# Logic_IO_Protection.net
KiCad netlist of a schematic drawn in Altium Designer
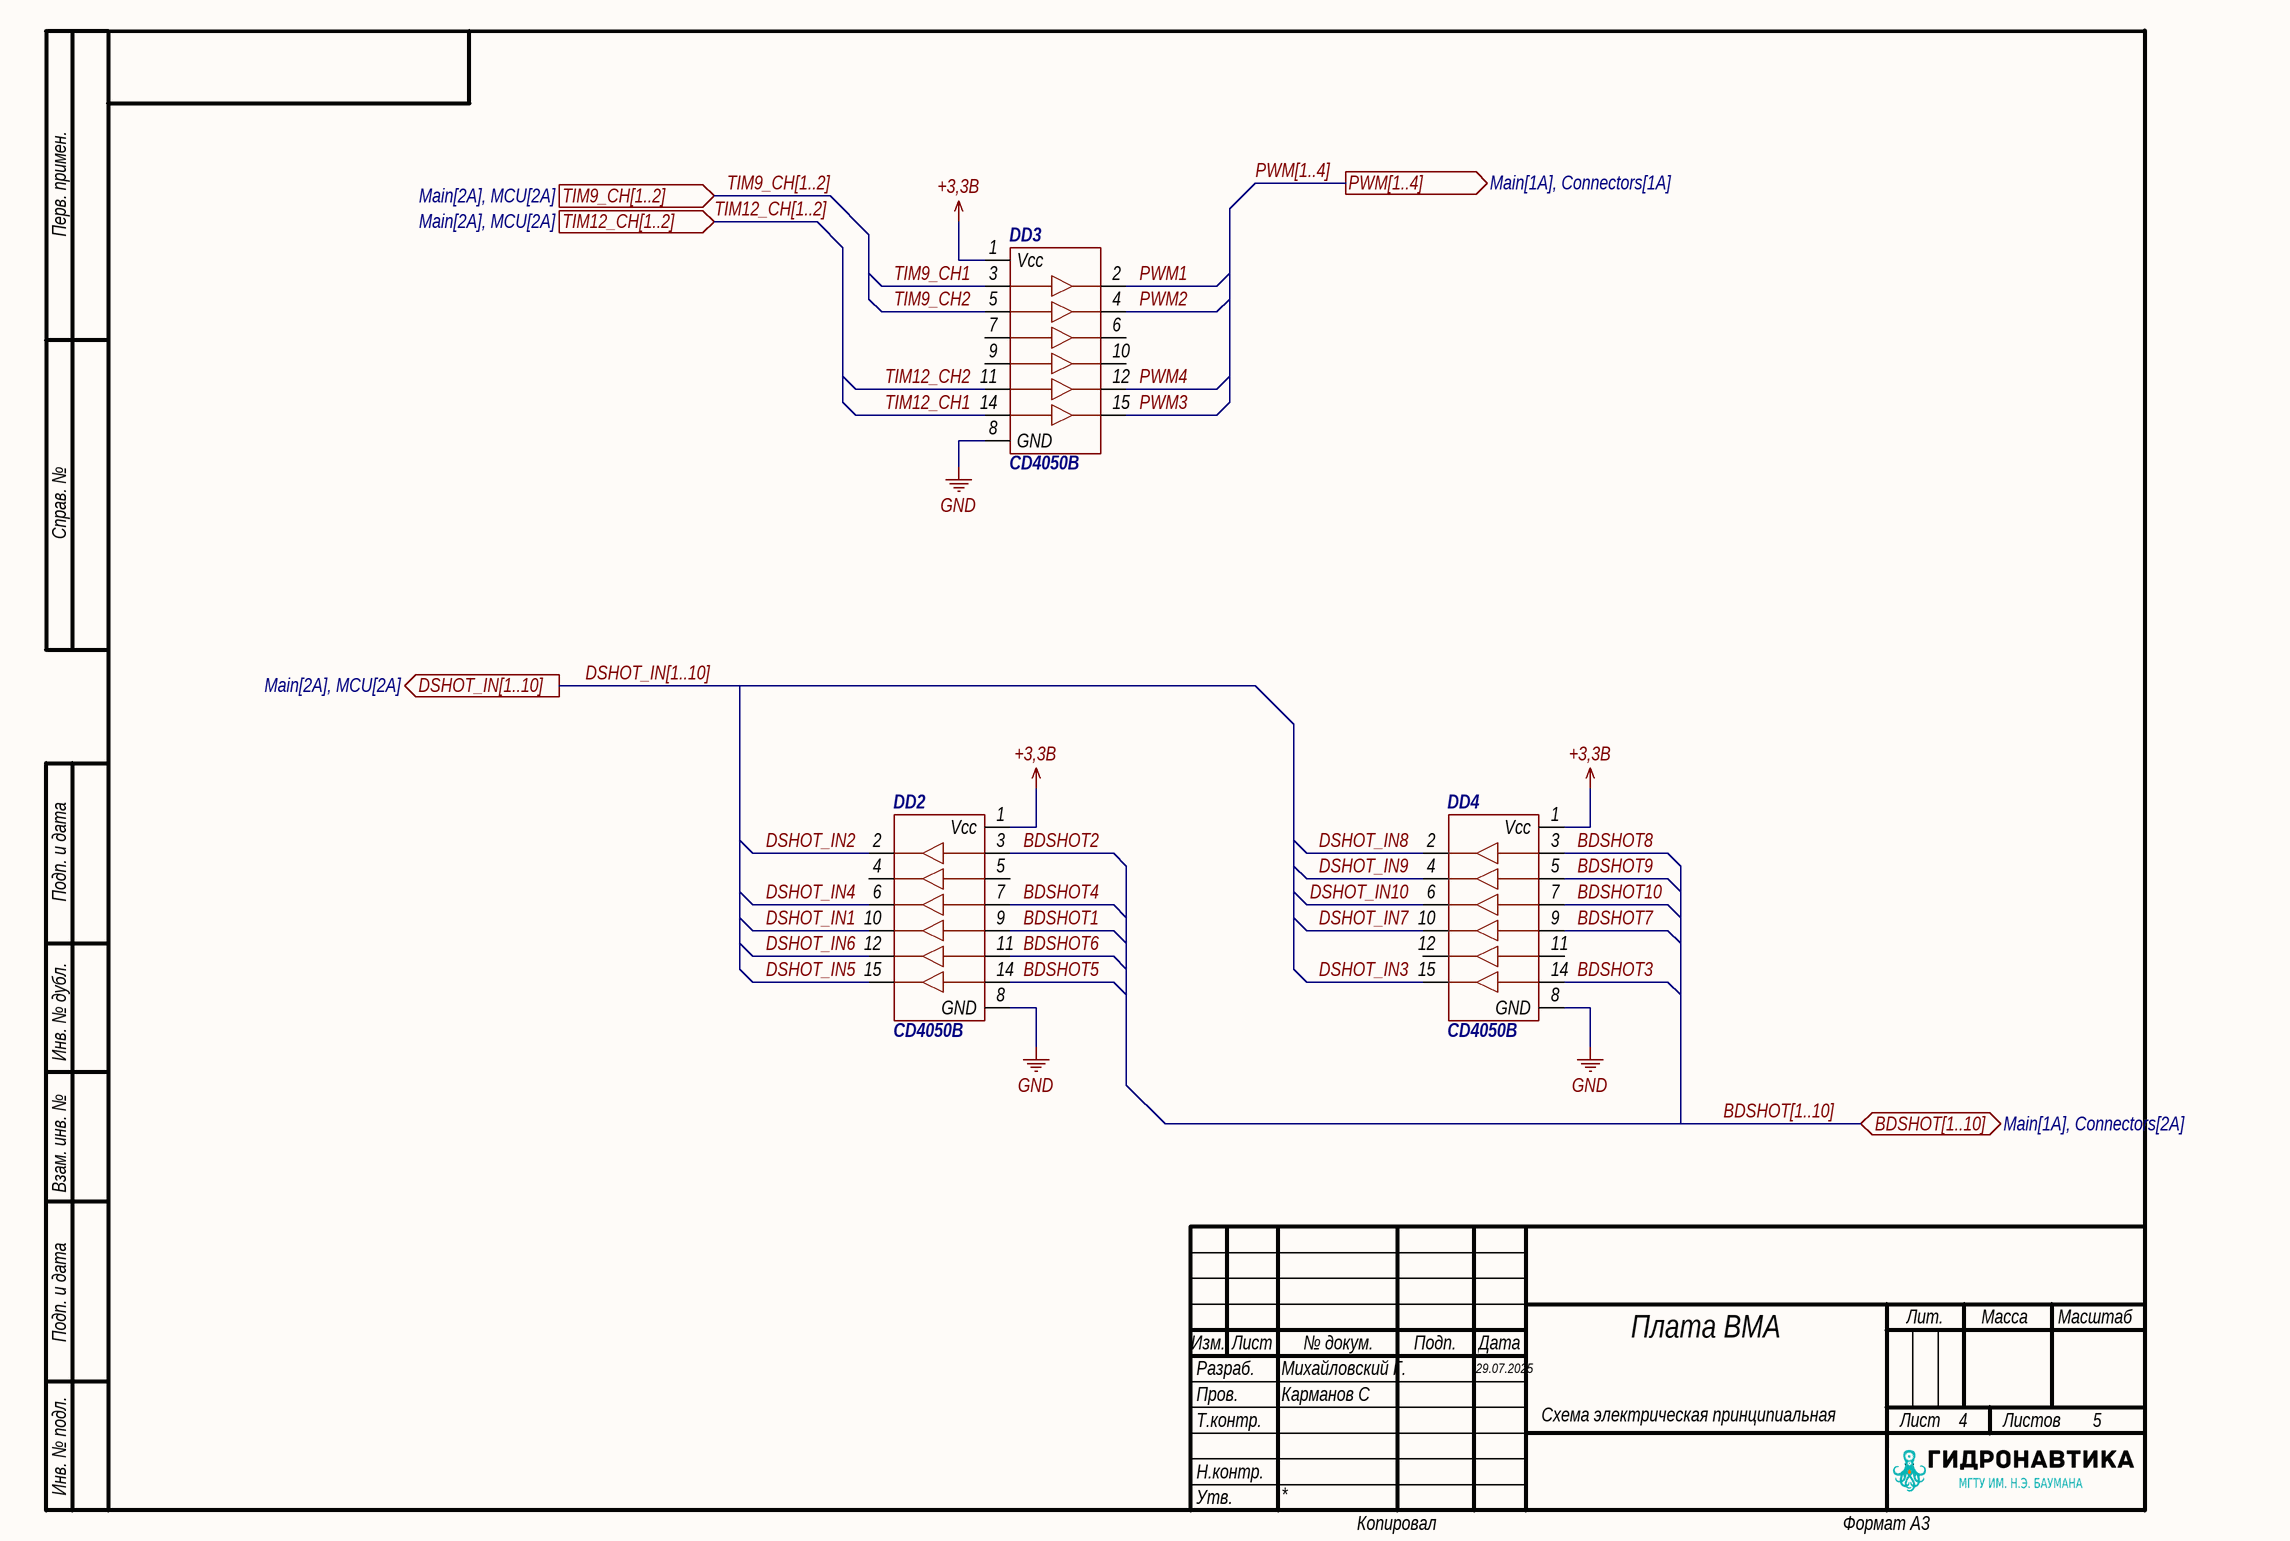
[diagram p0: Logic_IO_Protection.SchDoc]

(export (version "E")
  (design (tool "Eeschema 10.0.6"))
  (components
    (comp (ref "DD2")
      (value "CD4050B")
      (footprint "SOIC-16")
      (description "Шесть буферных элементов")
      (libsource (lib "") (part "CD4050B_1"))
    )
    (comp (ref "DD3")
      (value "CD4050B")
      (footprint "SOIC-16")
      (description "Шесть буферных элементов")
      (libsource (lib "Hydrolib") (part "CD4050B"))
    )
    (comp (ref "DD4")
      (value "CD4050B")
      (footprint "SOIC-16")
      (description "Шесть буферных элементов")
      (libsource (lib "") (part "CD4050B_1"))
    )
  )
  (nets
    (net (code "1") (name "+3,3В") (class "Default")
      (node (ref "DD2") (pin "1") (pinfunction "Vcc_1") (pintype "passive"))
      (node (ref "DD3") (pin "1") (pinfunction "Vcc_1") (pintype "passive"))
      (node (ref "DD4") (pin "1") (pinfunction "Vcc_1") (pintype "passive"))
    )
    (net (code "2") (name "/BDSHOT1") (class "Default")
      (node (ref "DD2") (pin "9") (pinfunction "A4_9") (pintype "passive"))
    )
    (net (code "3") (name "/BDSHOT2") (class "Default")
      (node (ref "DD2") (pin "3") (pinfunction "A1_3") (pintype "passive"))
    )
    (net (code "4") (name "/BDSHOT3") (class "Default")
      (node (ref "DD4") (pin "14") (pinfunction "A6_14") (pintype "passive"))
    )
    (net (code "5") (name "/BDSHOT4") (class "Default")
      (node (ref "DD2") (pin "7") (pinfunction "A3_7") (pintype "passive"))
    )
    (net (code "6") (name "/BDSHOT5") (class "Default")
      (node (ref "DD2") (pin "14") (pinfunction "A6_14") (pintype "passive"))
    )
    (net (code "7") (name "/BDSHOT6") (class "Default")
      (node (ref "DD2") (pin "11") (pinfunction "A5_11") (pintype "passive"))
    )
    (net (code "8") (name "/BDSHOT7") (class "Default")
      (node (ref "DD4") (pin "9") (pinfunction "A4_9") (pintype "passive"))
    )
    (net (code "9") (name "/BDSHOT8") (class "Default")
      (node (ref "DD4") (pin "3") (pinfunction "A1_3") (pintype "passive"))
    )
    (net (code "10") (name "/BDSHOT9") (class "Default")
      (node (ref "DD4") (pin "5") (pinfunction "A2_5") (pintype "passive"))
    )
    (net (code "11") (name "/BDSHOT10") (class "Default")
      (node (ref "DD4") (pin "7") (pinfunction "A3_7") (pintype "passive"))
    )
    (net (code "13") (name "/DSHOT_IN1") (class "Default")
      (node (ref "DD2") (pin "10") (pinfunction "Y10_10") (pintype "passive"))
    )
    (net (code "14") (name "/DSHOT_IN2") (class "Default")
      (node (ref "DD2") (pin "2") (pinfunction "Y1_2") (pintype "passive"))
    )
    (net (code "15") (name "/DSHOT_IN3") (class "Default")
      (node (ref "DD4") (pin "15") (pinfunction "Y6_15") (pintype "passive"))
    )
    (net (code "16") (name "/DSHOT_IN4") (class "Default")
      (node (ref "DD2") (pin "6") (pinfunction "Y3_6") (pintype "passive"))
    )
    (net (code "17") (name "/DSHOT_IN5") (class "Default")
      (node (ref "DD2") (pin "15") (pinfunction "Y6_15") (pintype "passive"))
    )
    (net (code "18") (name "/DSHOT_IN6") (class "Default")
      (node (ref "DD2") (pin "12") (pinfunction "Y5_12") (pintype "passive"))
    )
    (net (code "19") (name "/DSHOT_IN7") (class "Default")
      (node (ref "DD4") (pin "10") (pinfunction "Y10_10") (pintype "passive"))
    )
    (net (code "20") (name "/DSHOT_IN8") (class "Default")
      (node (ref "DD4") (pin "2") (pinfunction "Y1_2") (pintype "passive"))
    )
    (net (code "21") (name "/DSHOT_IN9") (class "Default")
      (node (ref "DD4") (pin "4") (pinfunction "Y2_4") (pintype "passive"))
    )
    (net (code "22") (name "/DSHOT_IN10") (class "Default")
      (node (ref "DD4") (pin "6") (pinfunction "Y3_6") (pintype "passive"))
    )
    (net (code "24") (name "/PWM1") (class "Default")
      (node (ref "DD3") (pin "2") (pinfunction "Y1_2") (pintype "passive"))
    )
    (net (code "25") (name "/PWM2") (class "Default")
      (node (ref "DD3") (pin "4") (pinfunction "Y2_4") (pintype "passive"))
    )
    (net (code "26") (name "/PWM3") (class "Default")
      (node (ref "DD3") (pin "15") (pinfunction "Y6_15") (pintype "passive"))
    )
    (net (code "27") (name "/PWM4") (class "Default")
      (node (ref "DD3") (pin "12") (pinfunction "Y5_12") (pintype "passive"))
    )
    (net (code "29") (name "/TIM9_CH1") (class "Default")
      (node (ref "DD3") (pin "3") (pinfunction "A1_3") (pintype "passive"))
    )
    (net (code "30") (name "/TIM9_CH2") (class "Default")
      (node (ref "DD3") (pin "5") (pinfunction "A2_5") (pintype "passive"))
    )
    (net (code "32") (name "/TIM12_CH1") (class "Default")
      (node (ref "DD3") (pin "14") (pinfunction "A6_14") (pintype "passive"))
    )
    (net (code "33") (name "/TIM12_CH2") (class "Default")
      (node (ref "DD3") (pin "11") (pinfunction "A5_11") (pintype "passive"))
    )
    (net (code "35") (name "GND") (class "Default")
      (node (ref "DD2") (pin "8") (pinfunction "GND_8") (pintype "passive"))
      (node (ref "DD3") (pin "8") (pinfunction "GND_8") (pintype "passive"))
      (node (ref "DD4") (pin "8") (pinfunction "GND_8") (pintype "passive"))
    )
    (net (code "36") (name "unconnected-(DD2-A2-Pad5)") (class "Default")
      (node (ref "DD2") (pin "5") (pinfunction "A2_5") (pintype "passive"))
    )
    (net (code "37") (name "unconnected-(DD2-Y2-Pad4)") (class "Default")
      (node (ref "DD2") (pin "4") (pinfunction "Y2_4") (pintype "passive"))
    )
    (net (code "38") (name "unconnected-(DD3-A3-Pad7)") (class "Default")
      (node (ref "DD3") (pin "7") (pinfunction "A3_7") (pintype "passive"))
    )
    (net (code "39") (name "unconnected-(DD3-A4-Pad9)") (class "Default")
      (node (ref "DD3") (pin "9") (pinfunction "A4_9") (pintype "passive"))
    )
    (net (code "40") (name "unconnected-(DD3-Y3-Pad6)") (class "Default")
      (node (ref "DD3") (pin "6") (pinfunction "Y3_6") (pintype "passive"))
    )
    (net (code "41") (name "unconnected-(DD3-Y10-Pad10)") (class "Default")
      (node (ref "DD3") (pin "10") (pinfunction "Y10_10") (pintype "passive"))
    )
    (net (code "42") (name "unconnected-(DD4-A5-Pad11)") (class "Default")
      (node (ref "DD4") (pin "11") (pinfunction "A5_11") (pintype "passive"))
    )
    (net (code "43") (name "unconnected-(DD4-Y5-Pad12)") (class "Default")
      (node (ref "DD4") (pin "12") (pinfunction "Y5_12") (pintype "passive"))
    )
  )
)
